# PUSH.net
KiCad netlist of a schematic drawn in Altium Designer
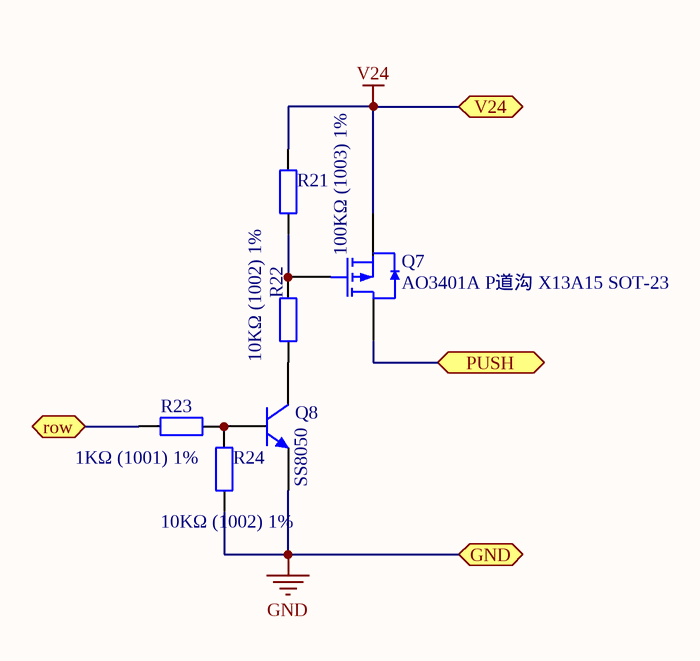
[diagram p0: PUSH.SchDoc]

(export (version "E")
  (design (tool "Eeschema 10.0.6"))
  (components
    (comp (ref "Q7")
      (value "AO3401A P道沟 X13A15 SOT-23")
      (footprint "SOT-23-3L")
      (description "MOS(场效应管)")
      (libsource (lib "Miscellaneous Devices LC") (part "AO3401A P道沟 X13A15 SOT-23"))
    )
    (comp (ref "Q8")
      (value "SS8050")
      (footprint "SOT-23(SOT-23-3)")
      (description "三极管")
      (libsource (lib "Miscellaneous Devices LC") (part "SOT-23 SS8050 Y1"))
    )
    (comp (ref "R21")
      (value "100KΩ (1003) 1%")
      (footprint "0805_R")
      (description "贴片电阻")
      (libsource (lib "Miscellaneous Devices LC") (part "0805 100KΩ (1003) 1%"))
    )
    (comp (ref "R22")
      (value "10KΩ (1002) 1%")
      (footprint "0805_R")
      (description "贴片电阻")
      (libsource (lib "") (part "0805 10KΩ (1002) 1%_1"))
    )
    (comp (ref "R23")
      (value "1KΩ (1001) 1%")
      (footprint "0805_R")
      (description "贴片电阻")
      (libsource (lib "Miscellaneous Devices LC") (part "0805 1KΩ (1001) 1%"))
    )
    (comp (ref "R24")
      (value "10KΩ (1002) 1%")
      (footprint "0805_R")
      (description "贴片电阻")
      (libsource (lib "Miscellaneous Devices LC") (part "0805 10KΩ (1002) 1%"))
    )
  )
  (nets
    (net (code "1") (name "/PUSH") (class "Default")
      (node (ref "Q7") (pin "3") (pinfunction "D_3") (pintype "passive"))
    )
    (net (code "2") (name "/row") (class "Default")
      (node (ref "R23") (pin "2") (pinfunction "2_2") (pintype "passive"))
    )
    (net (code "3") (name "GND") (class "Default")
      (node (ref "Q8") (pin "2") (pinfunction "E_2") (pintype "passive"))
      (node (ref "R24") (pin "2") (pinfunction "2_2") (pintype "passive"))
    )
    (net (code "4") (name "Net-(Q7-G)") (class "Default")
      (node (ref "Q7") (pin "1") (pinfunction "G_1") (pintype "passive"))
      (node (ref "R21") (pin "2") (pinfunction "2_2") (pintype "passive"))
      (node (ref "R22") (pin "2") (pinfunction "2_2") (pintype "passive"))
    )
    (net (code "5") (name "Net-(Q8-B)") (class "Default")
      (node (ref "Q8") (pin "1") (pinfunction "B_1") (pintype "passive"))
      (node (ref "R23") (pin "1") (pinfunction "1_1") (pintype "passive"))
      (node (ref "R24") (pin "1") (pinfunction "1_1") (pintype "passive"))
    )
    (net (code "6") (name "Net-(Q8-C)") (class "Default")
      (node (ref "Q8") (pin "3") (pinfunction "C_3") (pintype "passive"))
      (node (ref "R22") (pin "1") (pinfunction "1_1") (pintype "passive"))
    )
    (net (code "7") (name "V24") (class "Default")
      (node (ref "Q7") (pin "2") (pinfunction "S_2") (pintype "passive"))
      (node (ref "R21") (pin "1") (pinfunction "1_1") (pintype "passive"))
    )
  )
)
